# DCDC_1_rev3.net
KiCad netlist of a schematic drawn in Altium Designer
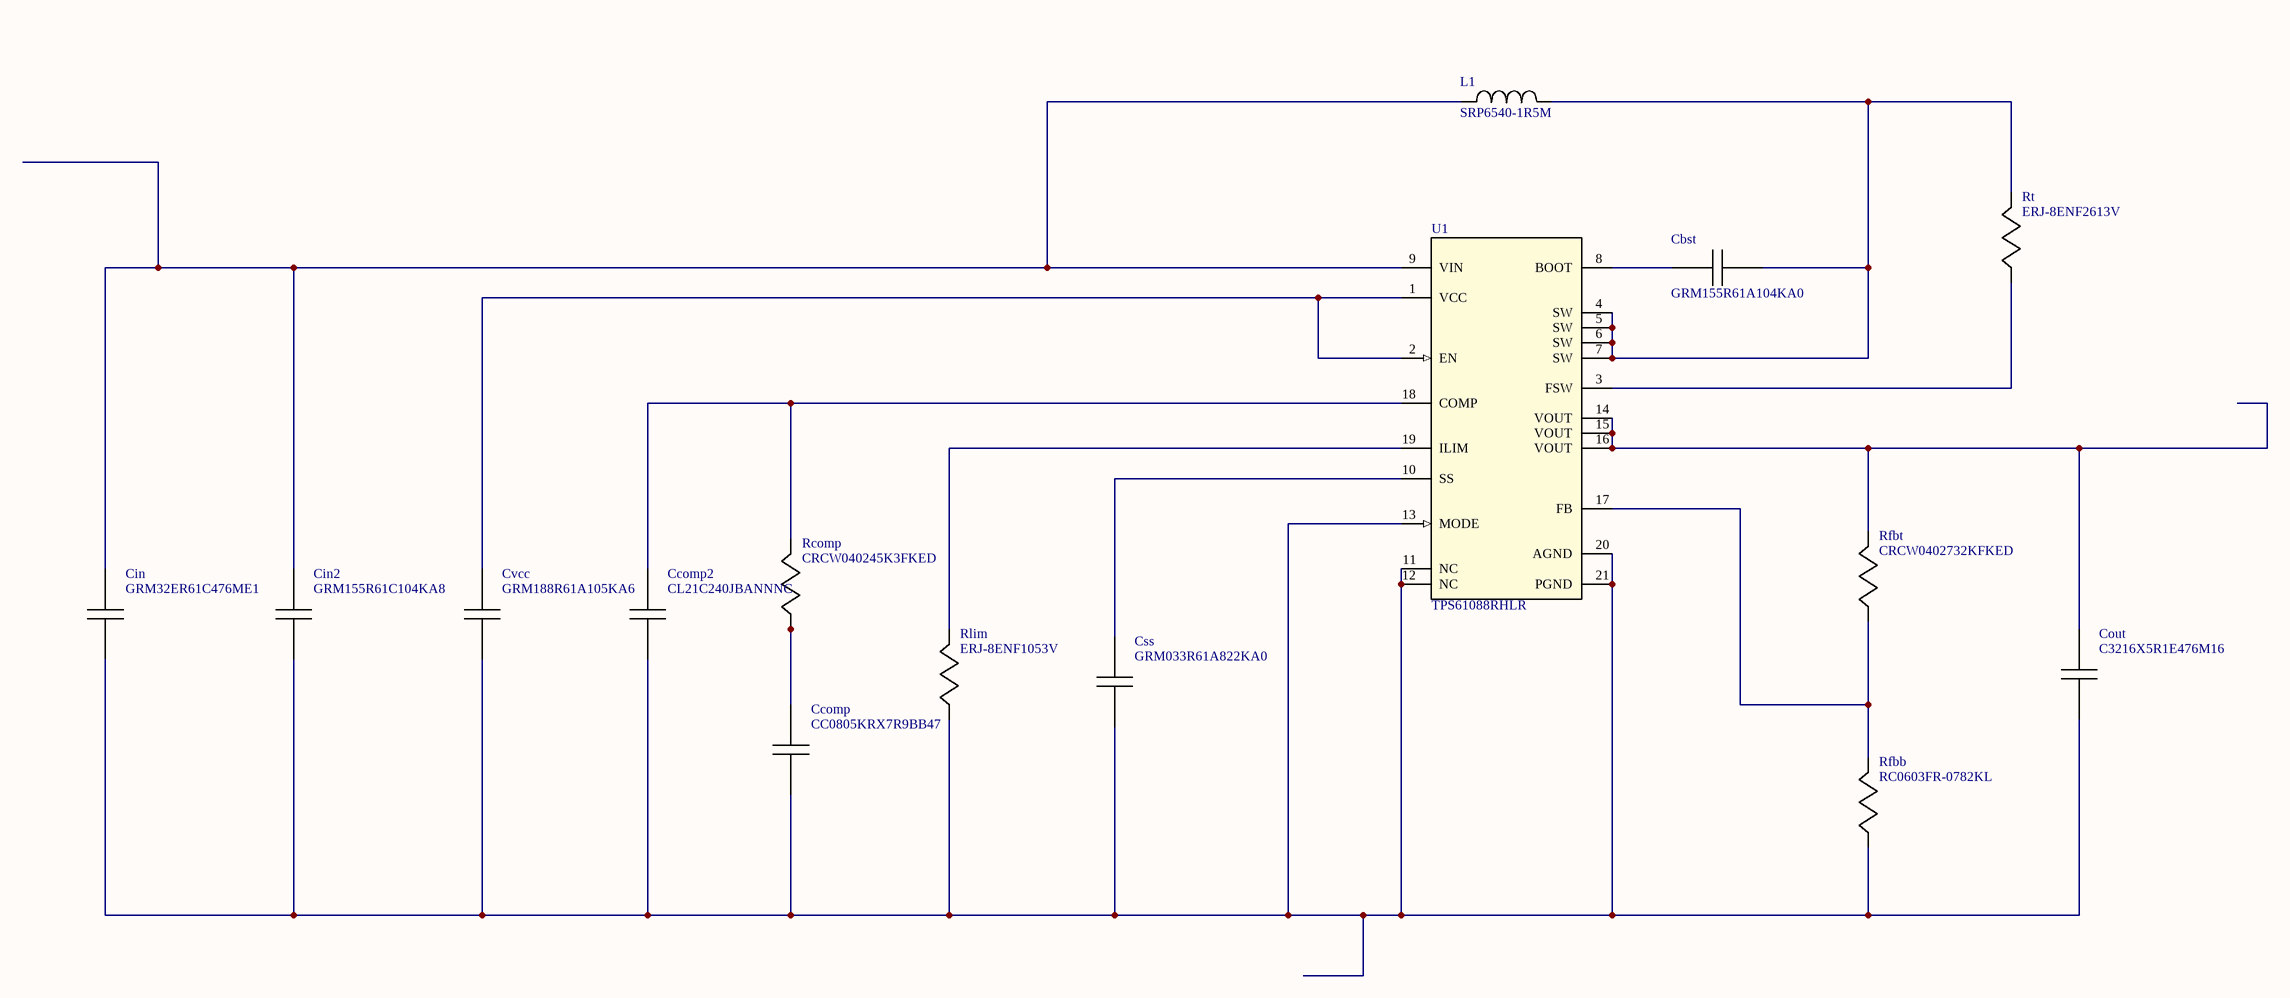
[diagram p0: DCDC_1_rev3.schdoc]

(export (version "E")
  (design (tool "Eeschema 10.0.6"))
  (components
    (comp (ref "Cbst")
      (value "GRM155R61A104KA0")
      (footprint "0402")
      (description "Imported")
      (fields (field (name "MANUFACTURER_PART_NUMBER") "GRM155R61A104KA01D"))
      (libsource (lib "2016-03-14_16-10-16") (part "GRM155R61A104KA0"))
    )
    (comp (ref "Ccomp")
      (value "CC0805KRX7R9BB47")
      (footprint "0805")
      (description "Imported")
      (fields (field (name "MANUFACTURER_PART_NUMBER") "CC0805KRX7R9BB471"))
      (libsource (lib "2016-03-14_16-10-16") (part "CC0805KRX7R9BB47"))
    )
    (comp (ref "Ccomp2")
      (value "CL21C240JBANNNC")
      (footprint "0805")
      (description "Imported")
      (libsource (lib "2016-03-14_16-10-16") (part "CL21C240JBANNNC"))
    )
    (comp (ref "Cin")
      (value "GRM32ER61C476ME1")
      (footprint "1210_280")
      (description "Imported")
      (fields (field (name "MANUFACTURER_PART_NUMBER") "GRM32ER61C476ME15L"))
      (libsource (lib "2016-03-14_16-10-16") (part "GRM32ER61C476ME1"))
    )
    (comp (ref "Cin2")
      (value "GRM155R61C104KA8")
      (footprint "0402")
      (description "Imported")
      (fields (field (name "MANUFACTURER_PART_NUMBER") "GRM155R61C104KA88D"))
      (libsource (lib "2016-03-14_16-10-16") (part "GRM155R61C104KA8"))
    )
    (comp (ref "Cout")
      (value "C3216X5R1E476M16")
      (footprint "1206_190")
      (description "Imported")
      (fields (field (name "MANUFACTURER_PART_NUMBER") "C3216X5R1E476M160AC"))
      (libsource (lib "2016-03-14_16-10-16") (part "C3216X5R1E476M16"))
    )
    (comp (ref "Css")
      (value "GRM033R61A822KA0")
      (footprint "0201")
      (description "Imported")
      (fields (field (name "MANUFACTURER_PART_NUMBER") "GRM033R61A822KA01D"))
      (libsource (lib "2016-03-14_16-10-16") (part "GRM033R61A822KA0"))
    )
    (comp (ref "Cvcc")
      (value "GRM188R61A105KA6")
      (footprint "0603")
      (description "Imported")
      (fields (field (name "MANUFACTURER_PART_NUMBER") "GRM188R61A105KA61D"))
      (libsource (lib "2016-03-14_16-10-16") (part "GRM188R61A105KA6"))
    )
    (comp (ref "L1")
      (value "SRP6540-1R5M")
      (footprint "SRP6540")
      (description "Imported")
      (fields (field (name "MANUFACTURER") "Bourns"))
      (libsource (lib "2016-03-14_16-10-16") (part "SRP6540-1R5M"))
    )
    (comp (ref "Rcomp")
      (value "CRCW040245K3FKED")
      (footprint "0402")
      (description "Imported")
      (libsource (lib "2016-03-14_16-10-16") (part "CRCW040245K3FKED"))
    )
    (comp (ref "Rfbb")
      (value "RC0603FR-0782KL")
      (footprint "0603")
      (description "Imported")
      (libsource (lib "2016-03-14_16-10-16") (part "RC0603FR-0782KL"))
    )
    (comp (ref "Rfbt")
      (value "CRCW0402732KFKED")
      (footprint "0402")
      (description "Imported")
      (libsource (lib "2016-03-14_16-10-16") (part "CRCW0402732KFKED"))
    )
    (comp (ref "Rlim")
      (value "ERJ-8ENF1053V")
      (footprint "1206")
      (description "Imported")
      (libsource (lib "2016-03-14_16-10-16") (part "ERJ-8ENF1053V"))
    )
    (comp (ref "Rt")
      (value "ERJ-8ENF2613V")
      (footprint "1206")
      (description "Imported")
      (libsource (lib "2016-03-14_16-10-16") (part "ERJ-8ENF2613V"))
    )
    (comp (ref "U1")
      (value "TPS61088RHLR")
      (footprint "RHL0020A")
      (description "Imported")
      (fields
        (field (name "ALTERNATE PARTNUMBER") "TPS61088RHLT")
        (field (name "MANUFACTURER") "Texas Instruments")
      )
      (libsource (lib "2016-03-14_16-10-16") (part "TPS61088RHLR"))
    )
  )
  (nets
    (net (code "1") (name "Net-(Cbst-Pad1)") (class "Default")
      (node (ref "Cbst") (pin "1") (pinfunction "1_1") (pintype "passive"))
      (node (ref "L1") (pin "2") (pinfunction "2_2") (pintype "passive"))
      (node (ref "Rt") (pin "1") (pinfunction "1_1") (pintype "passive"))
      (node (ref "U1") (pin "4") (pinfunction "SW_4") (pintype "power_in"))
      (node (ref "U1") (pin "5") (pinfunction "SW_5") (pintype "power_in"))
      (node (ref "U1") (pin "6") (pinfunction "SW_6") (pintype "power_in"))
      (node (ref "U1") (pin "7") (pinfunction "SW_7") (pintype "power_in"))
    )
    (net (code "2") (name "Net-(Ccomp-Pad1)") (class "Default")
      (node (ref "Ccomp") (pin "1") (pinfunction "1_1") (pintype "passive"))
      (node (ref "Rcomp") (pin "2") (pinfunction "2_2") (pintype "passive"))
    )
    (net (code "3") (name "Net-(Cout-Pad1)") (class "Default")
      (node (ref "Cout") (pin "1") (pinfunction "1_1") (pintype "passive"))
      (node (ref "Rfbt") (pin "1") (pinfunction "1_1") (pintype "passive"))
      (node (ref "U1") (pin "14") (pinfunction "VOUT_14") (pintype "passive"))
      (node (ref "U1") (pin "15") (pinfunction "VOUT_15") (pintype "passive"))
      (node (ref "U1") (pin "16") (pinfunction "VOUT_16") (pintype "passive"))
    )
    (net (code "4") (name "Net-(U1-AGND)") (class "Default")
      (node (ref "Ccomp") (pin "2") (pinfunction "2_2") (pintype "passive"))
      (node (ref "Ccomp2") (pin "2") (pinfunction "2_2") (pintype "passive"))
      (node (ref "Cin") (pin "2") (pinfunction "2_2") (pintype "passive"))
      (node (ref "Cin2") (pin "2") (pinfunction "2_2") (pintype "passive"))
      (node (ref "Cout") (pin "2") (pinfunction "2_2") (pintype "passive"))
      (node (ref "Css") (pin "2") (pinfunction "2_2") (pintype "passive"))
      (node (ref "Cvcc") (pin "2") (pinfunction "2_2") (pintype "passive"))
      (node (ref "Rfbb") (pin "2") (pinfunction "2_2") (pintype "passive"))
      (node (ref "Rlim") (pin "2") (pinfunction "2_2") (pintype "passive"))
      (node (ref "U1") (pin "11") (pinfunction "NC_11") (pintype "passive"))
      (node (ref "U1") (pin "12") (pinfunction "NC_12") (pintype "passive"))
      (node (ref "U1") (pin "13") (pinfunction "MODE_13") (pintype "input"))
      (node (ref "U1") (pin "20") (pinfunction "AGND_20") (pintype "passive"))
      (node (ref "U1") (pin "21") (pinfunction "PGND_21") (pintype "passive"))
    )
    (net (code "5") (name "Net-(U1-BOOT)") (class "Default")
      (node (ref "Cbst") (pin "2") (pinfunction "2_2") (pintype "passive"))
      (node (ref "U1") (pin "8") (pinfunction "BOOT_8") (pintype "power_in"))
    )
    (net (code "6") (name "Net-(U1-COMP)") (class "Default")
      (node (ref "Ccomp2") (pin "1") (pinfunction "1_1") (pintype "passive"))
      (node (ref "Rcomp") (pin "1") (pinfunction "1_1") (pintype "passive"))
      (node (ref "U1") (pin "18") (pinfunction "COMP_18") (pintype "passive"))
    )
    (net (code "7") (name "Net-(U1-EN)") (class "Default")
      (node (ref "Cvcc") (pin "1") (pinfunction "1_1") (pintype "passive"))
      (node (ref "U1") (pin "1") (pinfunction "VCC_1") (pintype "power_in"))
      (node (ref "U1") (pin "2") (pinfunction "EN_2") (pintype "input"))
    )
    (net (code "8") (name "Net-(U1-FB)") (class "Default")
      (node (ref "Rfbb") (pin "1") (pinfunction "1_1") (pintype "passive"))
      (node (ref "Rfbt") (pin "2") (pinfunction "2_2") (pintype "passive"))
      (node (ref "U1") (pin "17") (pinfunction "FB_17") (pintype "passive"))
    )
    (net (code "9") (name "Net-(U1-FSW)") (class "Default")
      (node (ref "Rt") (pin "2") (pinfunction "2_2") (pintype "passive"))
      (node (ref "U1") (pin "3") (pinfunction "FSW_3") (pintype "passive"))
    )
    (net (code "10") (name "Net-(U1-ILIM)") (class "Default")
      (node (ref "Rlim") (pin "1") (pinfunction "1_1") (pintype "passive"))
      (node (ref "U1") (pin "19") (pinfunction "ILIM_19") (pintype "passive"))
    )
    (net (code "11") (name "Net-(U1-SS)") (class "Default")
      (node (ref "Css") (pin "1") (pinfunction "1_1") (pintype "passive"))
      (node (ref "U1") (pin "10") (pinfunction "SS_10") (pintype "passive"))
    )
    (net (code "12") (name "Net-(U1-VIN)") (class "Default")
      (node (ref "Cin") (pin "1") (pinfunction "1_1") (pintype "passive"))
      (node (ref "Cin2") (pin "1") (pinfunction "1_1") (pintype "passive"))
      (node (ref "L1") (pin "1") (pinfunction "1_1") (pintype "passive"))
      (node (ref "U1") (pin "9") (pinfunction "VIN_9") (pintype "passive"))
    )
  )
)
